# Accumulator_DC-DC.net
KiCad netlist of a schematic drawn in Altium Designer
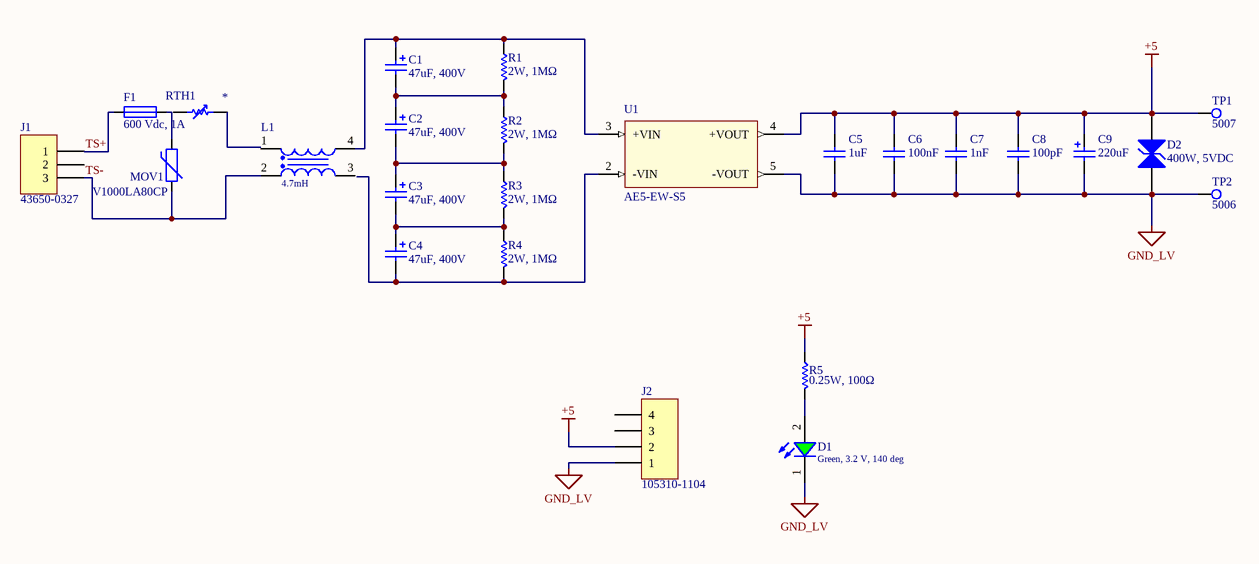
[diagram p0: Accumulator_DC-DC.SchDoc]

(export (version "E")
  (design (tool "Eeschema 10.0.6"))
  (components
    (comp (ref "C1")
      (value "47uF, 400V")
      (footprint "WCAP-ATG5_D16H25")
      (description "WCAP-ATG5 Aluminum Electrolytic Capacitor, Radial, THT, D16xH25, 47uF, 400V")
      (fields
        (field (name "MANUFACTURER PART NUMBER") "860021380015")
        (field (name "MANUFACTURER") "Wurth Elektronik")
      )
      (libsource (lib "WCAP-ATG5") (part "860021380015"))
    )
    (comp (ref "C2")
      (value "47uF, 400V")
      (footprint "WCAP-ATG5_D16H25")
      (description "WCAP-ATG5 Aluminum Electrolytic Capacitor, Radial, THT, D16xH25, 47uF, 400V")
      (fields
        (field (name "MANUFACTURER PART NUMBER") "860021380015")
        (field (name "MANUFACTURER") "Wurth Elektronik")
      )
      (libsource (lib "WCAP-ATG5") (part "860021380015"))
    )
    (comp (ref "C3")
      (value "47uF, 400V")
      (footprint "WCAP-ATG5_D16H25")
      (description "WCAP-ATG5 Aluminum Electrolytic Capacitor, Radial, THT, D16xH25, 47uF, 400V")
      (fields
        (field (name "MANUFACTURER PART NUMBER") "860021380015")
        (field (name "MANUFACTURER") "Wurth Elektronik")
      )
      (libsource (lib "WCAP-ATG5") (part "860021380015"))
    )
    (comp (ref "C4")
      (value "47uF, 400V")
      (footprint "WCAP-ATG5_D16H25")
      (description "WCAP-ATG5 Aluminum Electrolytic Capacitor, Radial, THT, D16xH25, 47uF, 400V")
      (fields
        (field (name "MANUFACTURER PART NUMBER") "860021380015")
        (field (name "MANUFACTURER") "Wurth Elektronik")
      )
      (libsource (lib "WCAP-ATG5") (part "860021380015"))
    )
    (comp (ref "C5")
      (value "1uF")
      (footprint "1206_3.2x1.6x1.15mm")
      (description "WCAP-CSGP Ceramic Capacitors, 1206, X7R, 10V, 1uF")
      (fields (field (name "PART NUMBER") "885012208013") (field (name "MANUFACTURER") "Wurth Elektronik"))
      (libsource (lib "Components_Library") (part "885012208013"))
    )
    (comp (ref "C6")
      (value "100nF")
      (footprint "1206_3.2x1.6x0.8mm")
      (description "WCAP-CSGP Ceramic Capacitors, 1206, X7R, 10V, 100nF")
      (fields (field (name "PART NUMBER") "885012208009") (field (name "MANUFACTURER") "Wurth Elektronik"))
      (libsource (lib "Components_Library") (part "885012208009"))
    )
    (comp (ref "C7")
      (value "1nF")
      (footprint "1206_3.2x1.6x0.8mm")
      (description "WCAP-CSGP Ceramic Capacitors, 1206, X7R, 10V, 1nF")
      (fields (field (name "PART NUMBER") "885012208006") (field (name "MANUFACTURER") "Wurth Elektronik"))
      (libsource (lib "Components_Library") (part "885012208006"))
    )
    (comp (ref "C8")
      (value "100pF")
      (footprint "1206_3.2x1.6x0.8mm")
      (description "WCAP-CSGP Ceramic Capacitors, 1206, NP0, 10V, 100pF")
      (fields (field (name "PART NUMBER") "885012008004") (field (name "MANUFACTURER") "Wurth Elektronik"))
      (libsource (lib "Components_Library") (part "885012008004"))
    )
    (comp (ref "C9")
      (value "220uF")
      (footprint "WCAP-ATG8_6.3x11x2.5")
      (description "WCAP-ATG8 Aluminum Electrolytic Capacitors, 6.3x11mm, 10 Vdc, 220 uF")
      (fields (field (name "PART NUMBER") "860010273009") (field (name "MANUFACTURER") "Wurth Elektronik"))
      (libsource (lib "Components_Library") (part "860010273009"))
    )
    (comp (ref "D1")
      (value "Green, 3.2 V, 140 deg")
      (footprint "WL-SMCW_1206")
      (description "SMT Mono-color Chip LED Waterclear WL-SMCW, size 1206, Green, 3.2 V, 140 deg, 450 mcd")
      (fields (field (name "PART NUMBER") "150120GS75000") (field (name "PUBLISHER") "Wurth Elektronik"))
      (libsource (lib "Components_Library") (part "150120GS75000"))
    )
    (comp (ref "D2")
      (value "400W, 5VDC")
      (footprint "WE-TVSP_DO-214AC_Bidirectional")
      (description "WE-TVSP Power TVS Diode, size DO-214AC, Bidirectional, 400 W, 5 VDC")
      (fields (field (name "PART NUMBER") "824501500") (field (name "MANUFACTURER") "Wurth Elektronik"))
      (libsource (lib "Components_Library") (part "824501500"))
    )
    (comp (ref "F1")
      (value "600 Vdc, 1A")
      (footprint "485001")
      (description "485 Series Fuse")
      (fields (field (name "MANUFACTURER") "Littlefuse"))
      (libsource (lib "Components_Library") (part "485001"))
    )
    (comp (ref "J1")
      (value "43650-0327")
      (footprint "43650-0327")
      (description "Micro-Fit 3.0 Vertical Header, 3.00mm Pitch, Single Row, 3 Circuits, Black")
      (fields (field (name "MANUFACTURER") "Molex"))
      (libsource (lib "Components_Library") (part "43650-0327"))
    )
    (comp (ref "J2")
      (value "105310-1104")
      (footprint "105310-1104")
      (description "Nano-Fit Vertical Header, Through Hole, 2.50mm Pitch, Dual Row, 4 Circuits, Black")
      (fields (field (name "MANUFACTURER") "Molex"))
      (libsource (lib "Components_Library") (part "105310-1104"))
    )
    (comp (ref "L1")
      (value "4.7mH")
      (footprint "WE-CMB HV_Type XXL_744831047068")
      (description "WE-CMB HV Common Mode Power Line Choke, Type XXL, 4.7mH, 6.8A, 760V")
      (fields
        (field (name "MANUFACTURER PART NUMBER") "744831047068")
        (field (name "MANUFACTURER") "Wurth Elektronik")
      )
      (libsource (lib "Altium_WE-CMBHV (rev20a)") (part "744831047068"))
    )
    (comp (ref "MOV1")
      (value "V1000LA80CP")
      (footprint "V1000LA160CP")
      (description "C-III Varistor Series")
      (fields (field (name "MANUFACTURER") "Littlefuse"))
      (libsource (lib "Components_Library") (part "V1000LA80CP"))
    )
    (comp (ref "R1")
      (value "2W, 1MΩ")
      (footprint "CR2512")
      (description "High Power Anti-Surge Chip Resistor")
      (fields (field (name "MANUFACTURER") "Bourns"))
      (libsource (lib "Components_Library") (part "CRS2512-FX-1004ELF"))
    )
    (comp (ref "R2")
      (value "2W, 1MΩ")
      (footprint "CR2512")
      (description "High Power Anti-Surge Chip Resistor")
      (fields (field (name "MANUFACTURER") "Bourns"))
      (libsource (lib "Components_Library") (part "CRS2512-FX-1004ELF"))
    )
    (comp (ref "R3")
      (value "2W, 1MΩ")
      (footprint "CR2512")
      (description "High Power Anti-Surge Chip Resistor")
      (fields (field (name "MANUFACTURER") "Bourns"))
      (libsource (lib "Components_Library") (part "CRS2512-FX-1004ELF"))
    )
    (comp (ref "R4")
      (value "2W, 1MΩ")
      (footprint "CR2512")
      (description "High Power Anti-Surge Chip Resistor")
      (fields (field (name "MANUFACTURER") "Bourns"))
      (libsource (lib "Components_Library") (part "CRS2512-FX-1004ELF"))
    )
    (comp (ref "R5")
      (value "0.25W, 100Ω")
      (footprint "CR1206")
      (description "Chip Resistor")
      (fields (field (name "MANUFACTURER") "Bourns"))
      (libsource (lib "Components_Library") (part "CR1206-FX-1000ELF"))
    )
    (comp (ref "RTH1")
      (value "Inrush_Current_Limiter")
      (footprint "Inrush_Current_Limiter")
      (description "THT NTC Inrush Current Limiter")
      (fields (field (name "TIME CONSTANT") "*"))
      (libsource (lib "BMS_18_19_library") (part "Inrush_Current_Limiter"))
    )
    (comp (ref "TP1")
      (value "5007")
      (footprint "5007")
      (description "Compact THM Test Point, White")
      (fields (field (name "MANUFACTURER") "Keystone Electronics"))
      (libsource (lib "Components_Library") (part "5007"))
    )
    (comp (ref "TP2")
      (value "5006")
      (footprint "5006")
      (description "Compact THM Test Point, Black")
      (fields (field (name "MANUFACTURER") "Keystone Electronics"))
      (libsource (lib "Components_Library") (part "5006"))
    )
    (comp (ref "U1")
      (value "AE5-EW-S5")
      (footprint "AE5-EW-S5")
      (description "Ultra Wide Voltage Input DC-DC Converter")
      (fields (field (name "MANUFACTURER") "CUI INC"))
      (libsource (lib "Components_Library") (part "AE5-EW-S5"))
    )
  )
  (nets
    (net (code "1") (name "+5") (class "Default")
      (node (ref "C5") (pin "2") (pinfunction "2_2") (pintype "passive"))
      (node (ref "C6") (pin "2") (pinfunction "2_2") (pintype "passive"))
      (node (ref "C7") (pin "2") (pinfunction "2_2") (pintype "passive"))
      (node (ref "C8") (pin "2") (pinfunction "2_2") (pintype "passive"))
      (node (ref "C9") (pin "1") (pinfunction "P_1") (pintype "passive"))
      (node (ref "D2") (pin "2") (pinfunction "C_2") (pintype "passive"))
      (node (ref "J2") (pin "2") (pinfunction "2_2") (pintype "passive"))
      (node (ref "R5") (pin "2") (pinfunction "2_2") (pintype "passive"))
      (node (ref "TP1") (pin "0") (pinfunction "0_0") (pintype "passive"))
      (node (ref "U1") (pin "4") (pinfunction "+VOUT_4") (pintype "output"))
    )
    (net (code "2") (name "/TS+") (class "Default")
      (node (ref "F1") (pin "1") (pinfunction "1_1") (pintype "passive"))
      (node (ref "J1") (pin "1") (pinfunction "1_1") (pintype "passive"))
    )
    (net (code "4") (name "GND_LV") (class "Default")
      (node (ref "C5") (pin "1") (pinfunction "1_1") (pintype "passive"))
      (node (ref "C6") (pin "1") (pinfunction "1_1") (pintype "passive"))
      (node (ref "C7") (pin "1") (pinfunction "1_1") (pintype "passive"))
      (node (ref "C8") (pin "1") (pinfunction "1_1") (pintype "passive"))
      (node (ref "C9") (pin "2") (pinfunction "N_2") (pintype "passive"))
      (node (ref "D1") (pin "1") (pinfunction "K_1") (pintype "passive"))
      (node (ref "D2") (pin "1") (pinfunction "C_1") (pintype "passive"))
      (node (ref "J2") (pin "1") (pinfunction "1_1") (pintype "passive"))
      (node (ref "TP2") (pin "0") (pinfunction "0_0") (pintype "passive"))
      (node (ref "U1") (pin "5") (pinfunction "-VOUT_5") (pintype "output"))
    )
    (net (code "5") (name "Net-(C1-N)") (class "Default")
      (node (ref "C1") (pin "2") (pinfunction "N_2") (pintype "passive"))
      (node (ref "C2") (pin "1") (pinfunction "P_1") (pintype "passive"))
      (node (ref "R1") (pin "1") (pinfunction "1_1") (pintype "passive"))
      (node (ref "R2") (pin "2") (pinfunction "2_2") (pintype "passive"))
    )
    (net (code "6") (name "Net-(C1-P)") (class "Default")
      (node (ref "C1") (pin "1") (pinfunction "P_1") (pintype "passive"))
      (node (ref "L1") (pin "4") (pinfunction "4_4") (pintype "passive"))
      (node (ref "R1") (pin "2") (pinfunction "2_2") (pintype "passive"))
      (node (ref "U1") (pin "3") (pinfunction "+VIN_3") (pintype "input"))
    )
    (net (code "7") (name "Net-(C2-N)") (class "Default")
      (node (ref "C2") (pin "2") (pinfunction "N_2") (pintype "passive"))
      (node (ref "C3") (pin "1") (pinfunction "P_1") (pintype "passive"))
      (node (ref "R2") (pin "1") (pinfunction "1_1") (pintype "passive"))
      (node (ref "R3") (pin "2") (pinfunction "2_2") (pintype "passive"))
    )
    (net (code "8") (name "Net-(C3-N)") (class "Default")
      (node (ref "C3") (pin "2") (pinfunction "N_2") (pintype "passive"))
      (node (ref "C4") (pin "1") (pinfunction "P_1") (pintype "passive"))
      (node (ref "R3") (pin "1") (pinfunction "1_1") (pintype "passive"))
      (node (ref "R4") (pin "2") (pinfunction "2_2") (pintype "passive"))
    )
    (net (code "9") (name "Net-(C4-N)") (class "Default")
      (node (ref "C4") (pin "2") (pinfunction "N_2") (pintype "passive"))
      (node (ref "R4") (pin "1") (pinfunction "1_1") (pintype "passive"))
      (node (ref "U1") (pin "2") (pinfunction "-VIN_2") (pintype "input"))
    )
    (net (code "10") (name "Net-(D1-A)") (class "Default")
      (node (ref "D1") (pin "2") (pinfunction "A_2") (pintype "passive"))
      (node (ref "R5") (pin "1") (pinfunction "1_1") (pintype "passive"))
    )
    (net (code "11") (name "Net-(F1-Pad2)") (class "Default")
      (node (ref "F1") (pin "2") (pinfunction "2_2") (pintype "passive"))
      (node (ref "MOV1") (pin "2") (pinfunction "2_2") (pintype "passive"))
    )
    (net (code "12") (name "Net-(J1-Pad3)") (class "Default")
      (node (ref "J1") (pin "3") (pinfunction "3_3") (pintype "passive"))
      (node (ref "L1") (pin "2") (pinfunction "2_2") (pintype "passive"))
      (node (ref "MOV1") (pin "1") (pinfunction "1_1") (pintype "passive"))
    )
    (net (code "13") (name "unconnected-(J1-Pad2)") (class "Default")
      (node (ref "J1") (pin "2") (pinfunction "2_2") (pintype "passive"))
    )
    (net (code "14") (name "unconnected-(J2-Pad3)") (class "Default")
      (node (ref "J2") (pin "3") (pinfunction "3_3") (pintype "passive"))
    )
    (net (code "15") (name "unconnected-(J2-Pad4)") (class "Default")
      (node (ref "J2") (pin "4") (pinfunction "4_4") (pintype "passive"))
    )
    (net (code "16") (name "unconnected-(L1-Pad1)") (class "Default")
      (node (ref "L1") (pin "1") (pinfunction "1_1") (pintype "passive"))
    )
    (net (code "17") (name "unconnected-(L1-Pad3)") (class "Default")
      (node (ref "L1") (pin "3") (pinfunction "3_3") (pintype "passive"))
    )
    (net (code "18") (name "unconnected-(RTH1-Pad1)") (class "Default")
      (node (ref "RTH1") (pin "1") (pintype "passive"))
    )
    (net (code "19") (name "unconnected-(RTH1-Pad2)") (class "Default")
      (node (ref "RTH1") (pin "2") (pintype "passive"))
    )
  )
)
